# Yombonet.net
KiCad netlist of a schematic drawn in EAGLE
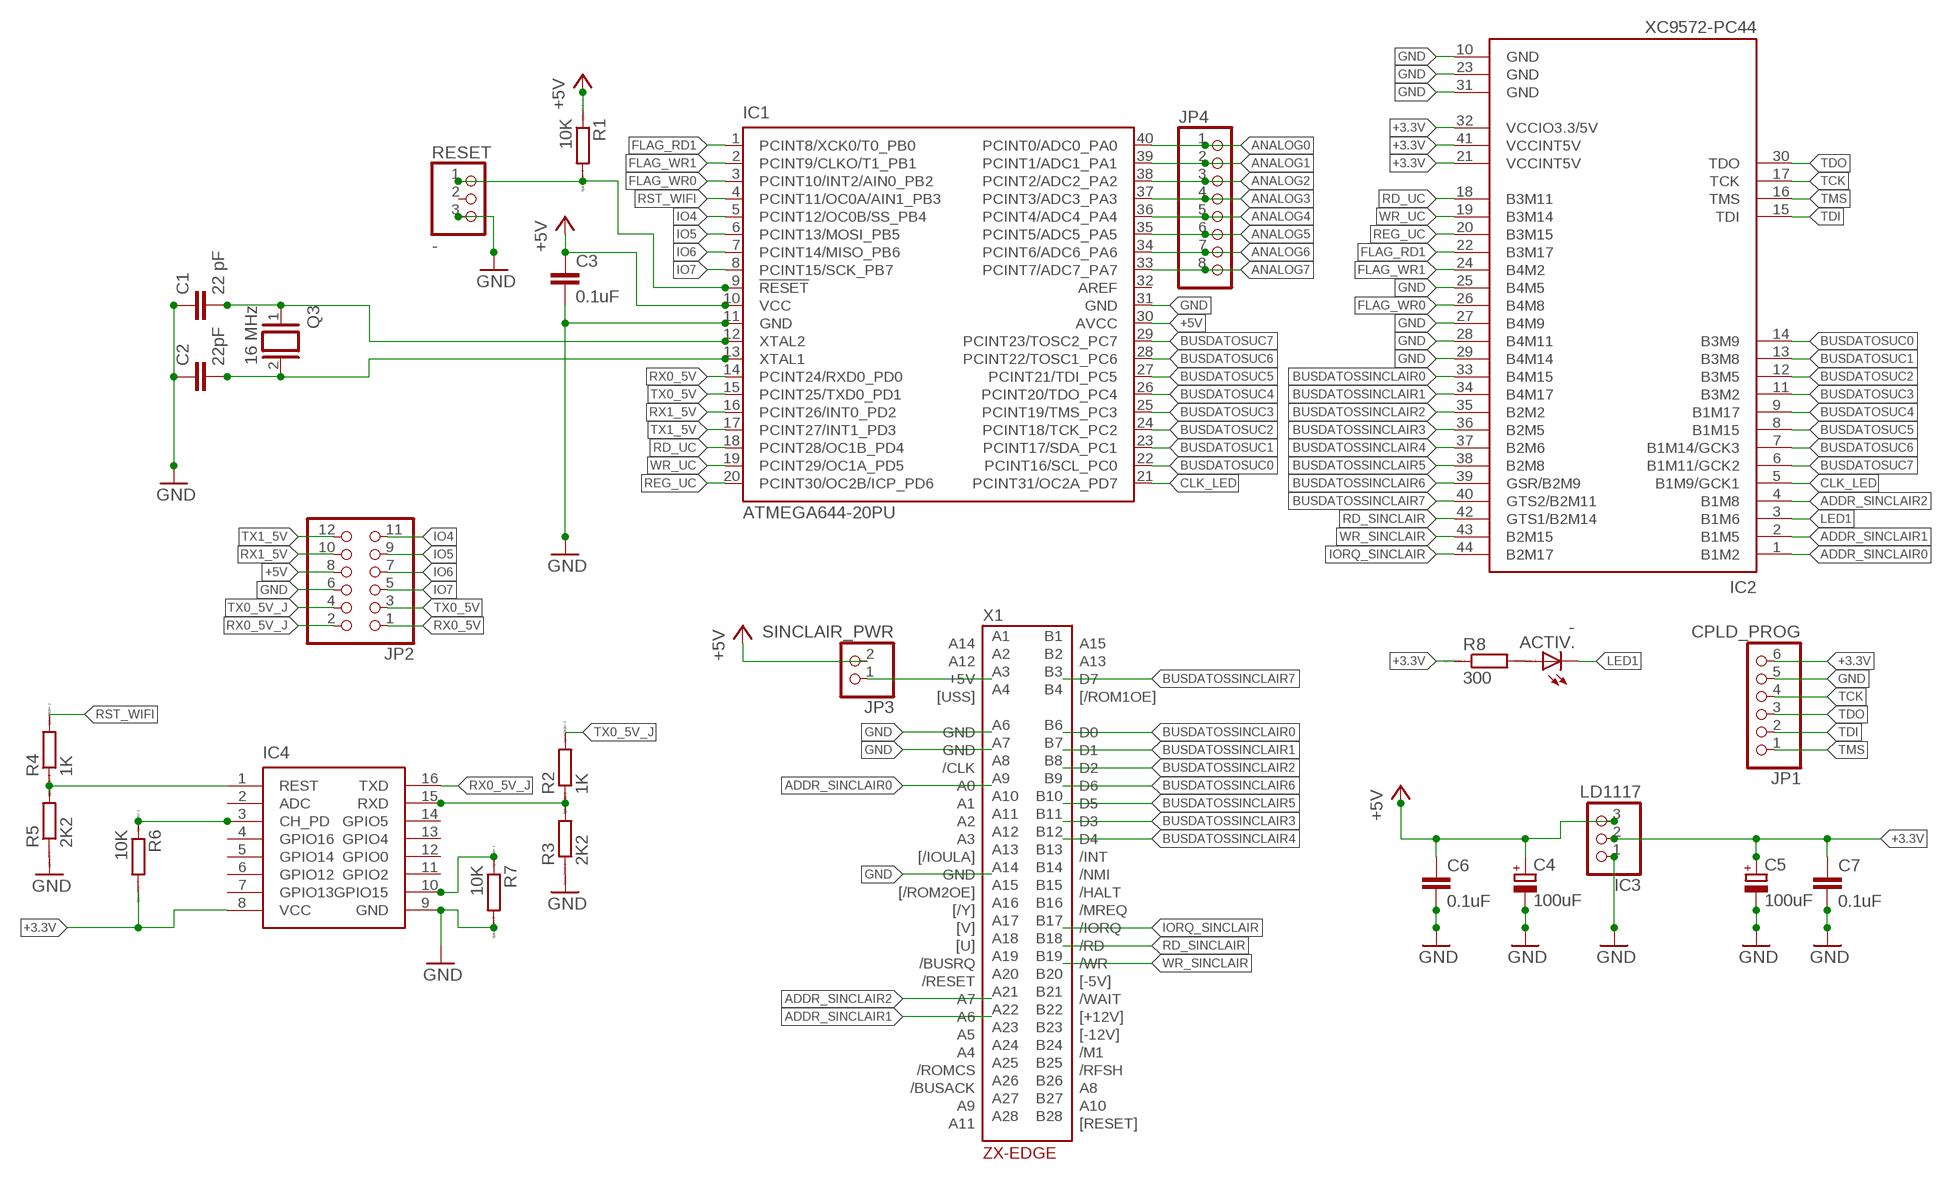
[diagram p0: schematic, sheet 1]

(export (version "E")
  (design (tool "Eeschema 10.0.6"))
  (components
    (comp (ref "ACTIV.")
      (value "-")
      (footprint "eagle-import:LED3MM")
      (libsource (lib "eagle-import") (part "LED3MM"))
    )
    (comp (ref "C1")
      (value "22 pF")
      (footprint "eagle-import:C025-024X044")
      (libsource (lib "eagle-import") (part "C-EU025-024X044"))
    )
    (comp (ref "C2")
      (value "22pF")
      (footprint "eagle-import:C025-024X044")
      (libsource (lib "eagle-import") (part "C-EU025-024X044"))
    )
    (comp (ref "C3")
      (value "0.1uF")
      (footprint "eagle-import:C025-025X050")
      (libsource (lib "eagle-import") (part "C-EU025-025X050"))
    )
    (comp (ref "C4")
      (value "100uF")
      (footprint "eagle-import:E2,5-7")
      (libsource (lib "eagle-import") (part "CPOL-EUE2.5-7"))
    )
    (comp (ref "C5")
      (value "100uF")
      (footprint "eagle-import:E2,5-7")
      (libsource (lib "eagle-import") (part "CPOL-EUE2.5-7"))
    )
    (comp (ref "C6")
      (value "0.1uF")
      (footprint "eagle-import:C025-025X050")
      (libsource (lib "eagle-import") (part "C-EU025-025X050"))
    )
    (comp (ref "C7")
      (value "0.1uF")
      (footprint "eagle-import:C025-025X050")
      (libsource (lib "eagle-import") (part "C-EU025-025X050"))
    )
    (comp (ref "IC1")
      (value "ATMEGA644-20PU")
      (footprint "eagle-import:DIL40")
      (libsource (lib "eagle-import") (part "ATMEGA644-PU20"))
    )
    (comp (ref "IC2")
      (value "XC9572-PC44")
      (footprint "eagle-import:PLCC-S44")
      (libsource (lib "eagle-import") (part "XC9572-PC44"))
    )
    (comp (ref "IC3")
      (value "LD1117")
      (footprint "eagle-import:1X03")
      (libsource (lib "eagle-import") (part "PINHD-1X3"))
    )
    (comp (ref "IC4")
      (value "ESP-07ESP-07")
      (footprint "eagle-import:ESP-07")
      (libsource (lib "eagle-import") (part "ESP-07ESP-07"))
    )
    (comp (ref "JP1")
      (value "CPLD_PROG")
      (footprint "eagle-import:1X06")
      (libsource (lib "eagle-import") (part "PINHD-1X6"))
    )
    (comp (ref "JP2")
      (value "PINHD-2X6")
      (footprint "eagle-import:2X06")
      (libsource (lib "eagle-import") (part "PINHD-2X6"))
    )
    (comp (ref "JP3")
      (value "SINCLAIR_PWR")
      (footprint "eagle-import:1X02")
      (libsource (lib "eagle-import") (part "PINHD-1X2"))
    )
    (comp (ref "JP4")
      (value "PINHD-1X8")
      (footprint "eagle-import:1X08")
      (libsource (lib "eagle-import") (part "PINHD-1X8"))
    )
    (comp (ref "Q3")
      (value "16 MHz")
      (footprint "eagle-import:QS")
      (libsource (lib "eagle-import") (part "XTAL/S"))
    )
    (comp (ref "R1")
      (value "10K")
      (footprint "eagle-import:0207_10")
      (libsource (lib "eagle-import") (part "R-EU_0207_10"))
    )
    (comp (ref "R2")
      (value "1K")
      (footprint "eagle-import:0207_10")
      (libsource (lib "eagle-import") (part "R-EU_0207_10"))
    )
    (comp (ref "R3")
      (value "2K2")
      (footprint "eagle-import:0207_10")
      (libsource (lib "eagle-import") (part "R-EU_0207_10"))
    )
    (comp (ref "R4")
      (value "1K")
      (footprint "eagle-import:0207_10")
      (libsource (lib "eagle-import") (part "R-EU_0207_10"))
    )
    (comp (ref "R5")
      (value "2K2")
      (footprint "eagle-import:0207_10")
      (libsource (lib "eagle-import") (part "R-EU_0207_10"))
    )
    (comp (ref "R6")
      (value "10K")
      (footprint "eagle-import:0207_10")
      (libsource (lib "eagle-import") (part "R-EU_0207_10"))
    )
    (comp (ref "R7")
      (value "10K")
      (footprint "eagle-import:0207_10")
      (libsource (lib "eagle-import") (part "R-EU_0207_10"))
    )
    (comp (ref "R8")
      (value "300")
      (footprint "eagle-import:0207_10")
      (libsource (lib "eagle-import") (part "R-EU_0207_10"))
    )
    (comp (ref "RESET")
      (value "-")
      (footprint "eagle-import:1X03")
      (libsource (lib "eagle-import") (part "PINHD-1X3"))
    )
    (comp (ref "X1")
      (value "ZX-EDGE")
      (footprint "eagle-import:ZX-IFACE")
      (libsource (lib "eagle-import") (part "ZX-EDGE"))
    )
  )
  (nets
    (net (code "1") (name "+3.3V") (class "Default")
      (node (ref "C5") (pin "+") (pinfunction "+_+") (pintype "passive"))
      (node (ref "C7") (pin "1") (pinfunction "1_1") (pintype "passive"))
      (node (ref "IC2") (pin "21") (pinfunction "VCCINT5V_21") (pintype "bidirectional"))
      (node (ref "IC2") (pin "32") (pinfunction "VCCIO3.3/5V_32") (pintype "bidirectional"))
      (node (ref "IC2") (pin "41") (pinfunction "VCCINT5V_41") (pintype "bidirectional"))
      (node (ref "IC3") (pin "2") (pinfunction "2_2") (pintype "passive"))
      (node (ref "IC4") (pin "8") (pinfunction "VCC_8") (pintype "power_in"))
      (node (ref "JP1") (pin "6") (pinfunction "6_6") (pintype "passive"))
      (node (ref "R6") (pin "2") (pinfunction "2_2") (pintype "passive"))
      (node (ref "R8") (pin "1") (pinfunction "1_1") (pintype "passive"))
    )
    (net (code "2") (name "+5V") (class "Default")
      (node (ref "C3") (pin "1") (pinfunction "1_1") (pintype "passive"))
      (node (ref "C4") (pin "+") (pinfunction "+_+") (pintype "passive"))
      (node (ref "C6") (pin "1") (pinfunction "1_1") (pintype "passive"))
      (node (ref "IC1") (pin "10") (pinfunction "VCC_10") (pintype "power_in"))
      (node (ref "IC1") (pin "30") (pinfunction "AVCC_30") (pintype "power_in"))
      (node (ref "IC3") (pin "3") (pinfunction "3_3") (pintype "passive"))
      (node (ref "JP2") (pin "8") (pinfunction "8_8") (pintype "passive"))
      (node (ref "JP3") (pin "2") (pinfunction "2_2") (pintype "passive"))
      (node (ref "R1") (pin "1") (pinfunction "1_1") (pintype "passive"))
    )
    (net (code "3") (name "ADDR_SINCLAIR0") (class "Default")
      (node (ref "IC2") (pin "1") (pinfunction "B1M2_1") (pintype "bidirectional"))
      (node (ref "X1") (pin "A9") (pinfunction "A0_A9") (pintype "bidirectional"))
    )
    (net (code "4") (name "ADDR_SINCLAIR1") (class "Default")
      (node (ref "IC2") (pin "2") (pinfunction "B1M5_2") (pintype "bidirectional"))
      (node (ref "X1") (pin "A22") (pinfunction "A6_A22") (pintype "bidirectional"))
    )
    (net (code "5") (name "ADDR_SINCLAIR2") (class "Default")
      (node (ref "IC2") (pin "4") (pinfunction "B1M8_4") (pintype "bidirectional"))
      (node (ref "X1") (pin "A21") (pinfunction "A7_A21") (pintype "bidirectional"))
    )
    (net (code "6") (name "ANALOG0") (class "Default")
      (node (ref "IC1") (pin "40") (pinfunction "PCINT0/ADC0_PA0_40") (pintype "bidirectional"))
      (node (ref "JP4") (pin "1") (pinfunction "1_1") (pintype "passive"))
    )
    (net (code "7") (name "ANALOG1") (class "Default")
      (node (ref "IC1") (pin "39") (pinfunction "PCINT1/ADC1_PA1_39") (pintype "bidirectional"))
      (node (ref "JP4") (pin "2") (pinfunction "2_2") (pintype "passive"))
    )
    (net (code "8") (name "ANALOG2") (class "Default")
      (node (ref "IC1") (pin "38") (pinfunction "PCINT2/ADC2_PA2_38") (pintype "bidirectional"))
      (node (ref "JP4") (pin "3") (pinfunction "3_3") (pintype "passive"))
    )
    (net (code "9") (name "ANALOG3") (class "Default")
      (node (ref "IC1") (pin "37") (pinfunction "PCINT3/ADC3_PA3_37") (pintype "bidirectional"))
      (node (ref "JP4") (pin "4") (pinfunction "4_4") (pintype "passive"))
    )
    (net (code "10") (name "ANALOG4") (class "Default")
      (node (ref "IC1") (pin "36") (pinfunction "PCINT4/ADC4_PA4_36") (pintype "bidirectional"))
      (node (ref "JP4") (pin "5") (pinfunction "5_5") (pintype "passive"))
    )
    (net (code "11") (name "ANALOG5") (class "Default")
      (node (ref "IC1") (pin "35") (pinfunction "PCINT5/ADC5_PA5_35") (pintype "bidirectional"))
      (node (ref "JP4") (pin "6") (pinfunction "6_6") (pintype "passive"))
    )
    (net (code "12") (name "ANALOG6") (class "Default")
      (node (ref "IC1") (pin "34") (pinfunction "PCINT6/ADC6_PA6_34") (pintype "bidirectional"))
      (node (ref "JP4") (pin "7") (pinfunction "7_7") (pintype "passive"))
    )
    (net (code "13") (name "ANALOG7") (class "Default")
      (node (ref "IC1") (pin "33") (pinfunction "PCINT7/ADC7_PA7_33") (pintype "bidirectional"))
      (node (ref "JP4") (pin "8") (pinfunction "8_8") (pintype "passive"))
    )
    (net (code "14") (name "BUSDATOSSINCLAIR0") (class "Default")
      (node (ref "IC2") (pin "33") (pinfunction "B4M15_33") (pintype "bidirectional"))
      (node (ref "X1") (pin "B6") (pinfunction "D0_B6") (pintype "bidirectional"))
    )
    (net (code "15") (name "BUSDATOSSINCLAIR1") (class "Default")
      (node (ref "IC2") (pin "34") (pinfunction "B4M17_34") (pintype "bidirectional"))
      (node (ref "X1") (pin "B7") (pinfunction "D1_B7") (pintype "bidirectional"))
    )
    (net (code "16") (name "BUSDATOSSINCLAIR2") (class "Default")
      (node (ref "IC2") (pin "35") (pinfunction "B2M2_35") (pintype "bidirectional"))
      (node (ref "X1") (pin "B8") (pinfunction "D2_B8") (pintype "bidirectional"))
    )
    (net (code "17") (name "BUSDATOSSINCLAIR3") (class "Default")
      (node (ref "IC2") (pin "36") (pinfunction "B2M5_36") (pintype "bidirectional"))
      (node (ref "X1") (pin "B11") (pinfunction "D3_B11") (pintype "bidirectional"))
    )
    (net (code "18") (name "BUSDATOSSINCLAIR4") (class "Default")
      (node (ref "IC2") (pin "37") (pinfunction "B2M6_37") (pintype "bidirectional"))
      (node (ref "X1") (pin "B12") (pinfunction "D4_B12") (pintype "bidirectional"))
    )
    (net (code "19") (name "BUSDATOSSINCLAIR5") (class "Default")
      (node (ref "IC2") (pin "38") (pinfunction "B2M8_38") (pintype "bidirectional"))
      (node (ref "X1") (pin "B10") (pinfunction "D5_B10") (pintype "bidirectional"))
    )
    (net (code "20") (name "BUSDATOSSINCLAIR6") (class "Default")
      (node (ref "IC2") (pin "39") (pinfunction "GSR/B2M9_39") (pintype "bidirectional"))
      (node (ref "X1") (pin "B9") (pinfunction "D6_B9") (pintype "bidirectional"))
    )
    (net (code "21") (name "BUSDATOSSINCLAIR7") (class "Default")
      (node (ref "IC2") (pin "40") (pinfunction "GTS2/B2M11_40") (pintype "bidirectional"))
      (node (ref "X1") (pin "B3") (pinfunction "D7_B3") (pintype "bidirectional"))
    )
    (net (code "22") (name "BUSDATOSUC0") (class "Default")
      (node (ref "IC1") (pin "22") (pinfunction "PCINT16/SCL_PC0_22") (pintype "bidirectional"))
      (node (ref "IC2") (pin "14") (pinfunction "B3M9_14") (pintype "bidirectional"))
    )
    (net (code "23") (name "BUSDATOSUC1") (class "Default")
      (node (ref "IC1") (pin "23") (pinfunction "PCINT17/SDA_PC1_23") (pintype "bidirectional"))
      (node (ref "IC2") (pin "13") (pinfunction "B3M8_13") (pintype "bidirectional"))
    )
    (net (code "24") (name "BUSDATOSUC2") (class "Default")
      (node (ref "IC1") (pin "24") (pinfunction "PCINT18/TCK_PC2_24") (pintype "bidirectional"))
      (node (ref "IC2") (pin "12") (pinfunction "B3M5_12") (pintype "bidirectional"))
    )
    (net (code "25") (name "BUSDATOSUC3") (class "Default")
      (node (ref "IC1") (pin "25") (pinfunction "PCINT19/TMS_PC3_25") (pintype "bidirectional"))
      (node (ref "IC2") (pin "11") (pinfunction "B3M2_11") (pintype "bidirectional"))
    )
    (net (code "26") (name "BUSDATOSUC4") (class "Default")
      (node (ref "IC1") (pin "26") (pinfunction "PCINT20/TDO_PC4_26") (pintype "bidirectional"))
      (node (ref "IC2") (pin "9") (pinfunction "B1M17_9") (pintype "bidirectional"))
    )
    (net (code "27") (name "BUSDATOSUC5") (class "Default")
      (node (ref "IC1") (pin "27") (pinfunction "PCINT21/TDI_PC5_27") (pintype "bidirectional"))
      (node (ref "IC2") (pin "8") (pinfunction "B1M15_8") (pintype "bidirectional"))
    )
    (net (code "28") (name "BUSDATOSUC6") (class "Default")
      (node (ref "IC1") (pin "28") (pinfunction "PCINT22/TOSC1_PC6_28") (pintype "bidirectional"))
      (node (ref "IC2") (pin "7") (pinfunction "B1M14/GCK3_7") (pintype "bidirectional"))
    )
    (net (code "29") (name "BUSDATOSUC7") (class "Default")
      (node (ref "IC1") (pin "29") (pinfunction "PCINT23/TOSC2_PC7_29") (pintype "bidirectional"))
      (node (ref "IC2") (pin "6") (pinfunction "B1M11/GCK2_6") (pintype "bidirectional"))
    )
    (net (code "30") (name "CLK_LED") (class "Default")
      (node (ref "IC1") (pin "21") (pinfunction "PCINT31/OC2A_PD7_21") (pintype "bidirectional"))
      (node (ref "IC2") (pin "5") (pinfunction "B1M9/GCK1_5") (pintype "bidirectional"))
    )
    (net (code "31") (name "FLAG_RD1") (class "Default")
      (node (ref "IC1") (pin "1") (pinfunction "PCINT8/XCK0/T0_PB0_1") (pintype "bidirectional"))
      (node (ref "IC2") (pin "22") (pinfunction "B3M17_22") (pintype "bidirectional"))
    )
    (net (code "32") (name "FLAG_WR0") (class "Default")
      (node (ref "IC1") (pin "3") (pinfunction "PCINT10/INT2/AIN0_PB2_3") (pintype "bidirectional"))
      (node (ref "IC2") (pin "26") (pinfunction "B4M8_26") (pintype "bidirectional"))
    )
    (net (code "33") (name "FLAG_WR1") (class "Default")
      (node (ref "IC1") (pin "2") (pinfunction "PCINT9/CLKO/T1_PB1_2") (pintype "bidirectional"))
      (node (ref "IC2") (pin "24") (pinfunction "B4M2_24") (pintype "bidirectional"))
    )
    (net (code "34") (name "GND") (class "Default")
      (node (ref "C1") (pin "1") (pinfunction "1_1") (pintype "passive"))
      (node (ref "C2") (pin "1") (pinfunction "1_1") (pintype "passive"))
      (node (ref "C3") (pin "2") (pinfunction "2_2") (pintype "passive"))
      (node (ref "C4") (pin "-") (pinfunction "-_-") (pintype "passive"))
      (node (ref "C5") (pin "-") (pinfunction "-_-") (pintype "passive"))
      (node (ref "C6") (pin "2") (pinfunction "2_2") (pintype "passive"))
      (node (ref "C7") (pin "2") (pinfunction "2_2") (pintype "passive"))
      (node (ref "IC1") (pin "11") (pinfunction "GND_11") (pintype "power_in"))
      (node (ref "IC1") (pin "31") (pinfunction "GND_31") (pintype "power_in"))
      (node (ref "IC2") (pin "10") (pinfunction "GND_10") (pintype "bidirectional"))
      (node (ref "IC2") (pin "23") (pinfunction "GND_23") (pintype "bidirectional"))
      (node (ref "IC2") (pin "25") (pinfunction "B4M5_25") (pintype "bidirectional"))
      (node (ref "IC2") (pin "27") (pinfunction "B4M9_27") (pintype "bidirectional"))
      (node (ref "IC2") (pin "28") (pinfunction "B4M11_28") (pintype "bidirectional"))
      (node (ref "IC2") (pin "29") (pinfunction "B4M14_29") (pintype "bidirectional"))
      (node (ref "IC2") (pin "31") (pinfunction "GND_31") (pintype "bidirectional"))
      (node (ref "IC3") (pin "1") (pinfunction "1_1") (pintype "passive"))
      (node (ref "IC4") (pin "9") (pinfunction "GND_9") (pintype "power_in"))
      (node (ref "JP1") (pin "5") (pinfunction "5_5") (pintype "passive"))
      (node (ref "JP2") (pin "6") (pinfunction "6_6") (pintype "passive"))
      (node (ref "R3") (pin "1") (pinfunction "1_1") (pintype "passive"))
      (node (ref "R5") (pin "1") (pinfunction "1_1") (pintype "passive"))
      (node (ref "R7") (pin "2") (pinfunction "2_2") (pintype "passive"))
      (node (ref "RESET") (pin "3") (pinfunction "3_3") (pintype "passive"))
      (node (ref "X1") (pin "A14") (pinfunction "GND_A14") (pintype "bidirectional"))
      (node (ref "X1") (pin "A6") (pinfunction "GND_A6") (pintype "bidirectional"))
      (node (ref "X1") (pin "A7") (pinfunction "GND_A7") (pintype "bidirectional"))
    )
    (net (code "35") (name "IO4") (class "Default")
      (node (ref "IC1") (pin "5") (pinfunction "PCINT12/OC0B/SS_PB4_5") (pintype "bidirectional"))
      (node (ref "JP2") (pin "11") (pinfunction "11_11") (pintype "passive"))
    )
    (net (code "36") (name "IO5") (class "Default")
      (node (ref "IC1") (pin "6") (pinfunction "PCINT13/MOSI_PB5_6") (pintype "bidirectional"))
      (node (ref "JP2") (pin "9") (pinfunction "9_9") (pintype "passive"))
    )
    (net (code "37") (name "IO6") (class "Default")
      (node (ref "IC1") (pin "7") (pinfunction "PCINT14/MISO_PB6_7") (pintype "bidirectional"))
      (node (ref "JP2") (pin "7") (pinfunction "7_7") (pintype "passive"))
    )
    (net (code "38") (name "IO7") (class "Default")
      (node (ref "IC1") (pin "8") (pinfunction "PCINT15/SCK_PB7_8") (pintype "bidirectional"))
      (node (ref "JP2") (pin "5") (pinfunction "5_5") (pintype "passive"))
    )
    (net (code "39") (name "IORQ_SINCLAIR") (class "Default")
      (node (ref "IC2") (pin "44") (pinfunction "B2M17_44") (pintype "bidirectional"))
      (node (ref "X1") (pin "B17") (pinfunction "/IORQ_B17") (pintype "bidirectional"))
    )
    (net (code "40") (name "LED1") (class "Default")
      (node (ref "ACTIV.") (pin "K") (pinfunction "C_K") (pintype "passive"))
      (node (ref "IC2") (pin "3") (pinfunction "B1M6_3") (pintype "bidirectional"))
    )
    (net (code "41") (name "Net-(ACTIV.-PadA)") (class "Default")
      (node (ref "ACTIV.") (pin "A") (pinfunction "A_A") (pintype "passive"))
      (node (ref "R8") (pin "2") (pinfunction "2_2") (pintype "passive"))
    )
    (net (code "42") (name "Net-(IC1-XTAL1)") (class "Default")
      (node (ref "C2") (pin "2") (pinfunction "2_2") (pintype "passive"))
      (node (ref "IC1") (pin "13") (pinfunction "XTAL1_13") (pintype "input"))
      (node (ref "Q3") (pin "2") (pinfunction "2_2") (pintype "passive"))
    )
    (net (code "43") (name "Net-(IC1-XTAL2)") (class "Default")
      (node (ref "C1") (pin "2") (pinfunction "2_2") (pintype "passive"))
      (node (ref "IC1") (pin "12") (pinfunction "XTAL2_12") (pintype "output"))
      (node (ref "Q3") (pin "1") (pinfunction "1_1") (pintype "passive"))
    )
    (net (code "44") (name "Net-(IC1-~{RESET})") (class "Default")
      (node (ref "IC1") (pin "9") (pinfunction "~{RESET}_9") (pintype "input"))
      (node (ref "R1") (pin "2") (pinfunction "2_2") (pintype "passive"))
      (node (ref "RESET") (pin "1") (pinfunction "1_1") (pintype "passive"))
    )
    (net (code "45") (name "Net-(IC4-CH_PD)") (class "Default")
      (node (ref "IC4") (pin "3") (pinfunction "CH_PD_3") (pintype "bidirectional"))
      (node (ref "R6") (pin "1") (pinfunction "1_1") (pintype "passive"))
    )
    (net (code "46") (name "Net-(IC4-GPIO15)") (class "Default")
      (node (ref "IC4") (pin "10") (pinfunction "GPIO15_10") (pintype "bidirectional"))
      (node (ref "R7") (pin "1") (pinfunction "1_1") (pintype "passive"))
    )
    (net (code "47") (name "Net-(IC4-REST)") (class "Default")
      (node (ref "IC4") (pin "1") (pinfunction "REST_1") (pintype "input"))
      (node (ref "R4") (pin "1") (pinfunction "1_1") (pintype "passive"))
      (node (ref "R5") (pin "2") (pinfunction "2_2") (pintype "passive"))
    )
    (net (code "48") (name "Net-(IC4-RXD)") (class "Default")
      (node (ref "IC4") (pin "15") (pinfunction "RXD_15") (pintype "input"))
      (node (ref "R2") (pin "1") (pinfunction "1_1") (pintype "passive"))
      (node (ref "R3") (pin "2") (pinfunction "2_2") (pintype "passive"))
    )
    (net (code "49") (name "Net-(X1-+5V)") (class "Default")
      (node (ref "JP3") (pin "1") (pinfunction "1_1") (pintype "passive"))
      (node (ref "X1") (pin "A3") (pinfunction "+5V_A3") (pintype "bidirectional"))
    )
    (net (code "50") (name "RD_SINCLAIR") (class "Default")
      (node (ref "IC2") (pin "42") (pinfunction "GTS1/B2M14_42") (pintype "bidirectional"))
      (node (ref "X1") (pin "B18") (pinfunction "/RD_B18") (pintype "bidirectional"))
    )
    (net (code "51") (name "RD_UC") (class "Default")
      (node (ref "IC1") (pin "18") (pinfunction "PCINT28/OC1B_PD4_18") (pintype "bidirectional"))
      (node (ref "IC2") (pin "18") (pinfunction "B3M11_18") (pintype "bidirectional"))
    )
    (net (code "52") (name "REG_UC") (class "Default")
      (node (ref "IC1") (pin "20") (pinfunction "PCINT30/OC2B/ICP_PD6_20") (pintype "bidirectional"))
      (node (ref "IC2") (pin "20") (pinfunction "B3M15_20") (pintype "bidirectional"))
    )
    (net (code "53") (name "RST_WIFI") (class "Default")
      (node (ref "IC1") (pin "4") (pinfunction "PCINT11/OC0A/AIN1_PB3_4") (pintype "bidirectional"))
      (node (ref "R4") (pin "2") (pinfunction "2_2") (pintype "passive"))
    )
    (net (code "54") (name "RX0_5V") (class "Default")
      (node (ref "IC1") (pin "14") (pinfunction "PCINT24/RXD0_PD0_14") (pintype "bidirectional"))
      (node (ref "JP2") (pin "1") (pinfunction "1_1") (pintype "passive"))
    )
    (net (code "55") (name "RX0_5V_J") (class "Default")
      (node (ref "IC4") (pin "16") (pinfunction "TXD_16") (pintype "output"))
      (node (ref "JP2") (pin "2") (pinfunction "2_2") (pintype "passive"))
    )
    (net (code "56") (name "RX1_5V") (class "Default")
      (node (ref "IC1") (pin "16") (pinfunction "PCINT26/INT0_PD2_16") (pintype "bidirectional"))
      (node (ref "JP2") (pin "10") (pinfunction "10_10") (pintype "passive"))
    )
    (net (code "57") (name "TCK") (class "Default")
      (node (ref "IC2") (pin "17") (pinfunction "TCK_17") (pintype "bidirectional"))
      (node (ref "JP1") (pin "4") (pinfunction "4_4") (pintype "passive"))
    )
    (net (code "58") (name "TDI") (class "Default")
      (node (ref "IC2") (pin "15") (pinfunction "TDI_15") (pintype "bidirectional"))
      (node (ref "JP1") (pin "2") (pinfunction "2_2") (pintype "passive"))
    )
    (net (code "59") (name "TDO") (class "Default")
      (node (ref "IC2") (pin "30") (pinfunction "TDO_30") (pintype "bidirectional"))
      (node (ref "JP1") (pin "3") (pinfunction "3_3") (pintype "passive"))
    )
    (net (code "60") (name "TMS") (class "Default")
      (node (ref "IC2") (pin "16") (pinfunction "TMS_16") (pintype "bidirectional"))
      (node (ref "JP1") (pin "1") (pinfunction "1_1") (pintype "passive"))
    )
    (net (code "61") (name "TX0_5V") (class "Default")
      (node (ref "IC1") (pin "15") (pinfunction "PCINT25/TXD0_PD1_15") (pintype "bidirectional"))
      (node (ref "JP2") (pin "3") (pinfunction "3_3") (pintype "passive"))
    )
    (net (code "62") (name "TX0_5V_J") (class "Default")
      (node (ref "JP2") (pin "4") (pinfunction "4_4") (pintype "passive"))
      (node (ref "R2") (pin "2") (pinfunction "2_2") (pintype "passive"))
    )
    (net (code "63") (name "TX1_5V") (class "Default")
      (node (ref "IC1") (pin "17") (pinfunction "PCINT27/INT1_PD3_17") (pintype "bidirectional"))
      (node (ref "JP2") (pin "12") (pinfunction "12_12") (pintype "passive"))
    )
    (net (code "64") (name "WR_SINCLAIR") (class "Default")
      (node (ref "IC2") (pin "43") (pinfunction "B2M15_43") (pintype "bidirectional"))
      (node (ref "X1") (pin "B19") (pinfunction "/WR_B19") (pintype "bidirectional"))
    )
    (net (code "65") (name "WR_UC") (class "Default")
      (node (ref "IC1") (pin "19") (pinfunction "PCINT29/OC1A_PD5_19") (pintype "bidirectional"))
      (node (ref "IC2") (pin "19") (pinfunction "B3M14_19") (pintype "bidirectional"))
    )
    (net (code "66") (name "unconnected-(IC1-AREF-Pad32)") (class "Default")
      (node (ref "IC1") (pin "32") (pinfunction "AREF_32") (pintype "passive"))
    )
    (net (code "67") (name "unconnected-(IC4-ADC-Pad2)") (class "Default")
      (node (ref "IC4") (pin "2") (pinfunction "ADC_2") (pintype "bidirectional"))
    )
    (net (code "68") (name "unconnected-(IC4-GPIO0-Pad12)") (class "Default")
      (node (ref "IC4") (pin "12") (pinfunction "GPIO0_12") (pintype "bidirectional"))
    )
    (net (code "69") (name "unconnected-(IC4-GPIO2-Pad11)") (class "Default")
      (node (ref "IC4") (pin "11") (pinfunction "GPIO2_11") (pintype "bidirectional"))
    )
    (net (code "70") (name "unconnected-(IC4-GPIO4-Pad13)") (class "Default")
      (node (ref "IC4") (pin "13") (pinfunction "GPIO4_13") (pintype "bidirectional"))
    )
    (net (code "71") (name "unconnected-(IC4-GPIO5-Pad14)") (class "Default")
      (node (ref "IC4") (pin "14") (pinfunction "GPIO5_14") (pintype "bidirectional"))
    )
    (net (code "72") (name "unconnected-(IC4-GPIO12-Pad6)") (class "Default")
      (node (ref "IC4") (pin "6") (pinfunction "GPIO12_6") (pintype "bidirectional"))
    )
    (net (code "73") (name "unconnected-(IC4-GPIO13-Pad7)") (class "Default")
      (node (ref "IC4") (pin "7") (pinfunction "GPIO13_7") (pintype "bidirectional"))
    )
    (net (code "74") (name "unconnected-(IC4-GPIO14-Pad5)") (class "Default")
      (node (ref "IC4") (pin "5") (pinfunction "GPIO14_5") (pintype "bidirectional"))
    )
    (net (code "75") (name "unconnected-(IC4-GPIO16-Pad4)") (class "Default")
      (node (ref "IC4") (pin "4") (pinfunction "GPIO16_4") (pintype "bidirectional"))
    )
    (net (code "76") (name "unconnected-(RESET-Pad2)") (class "Default")
      (node (ref "RESET") (pin "2") (pinfunction "2_2") (pintype "passive"))
    )
    (net (code "77") (name "unconnected-(X1-A1-PadA10)") (class "Default")
      (node (ref "X1") (pin "A10") (pinfunction "A1_A10") (pintype "bidirectional"))
    )
    (net (code "78") (name "unconnected-(X1-A2-PadA11)") (class "Default")
      (node (ref "X1") (pin "A11") (pinfunction "A2_A11") (pintype "bidirectional"))
    )
    (net (code "79") (name "unconnected-(X1-A3-PadA12)") (class "Default")
      (node (ref "X1") (pin "A12") (pinfunction "A3_A12") (pintype "bidirectional"))
    )
    (net (code "80") (name "unconnected-(X1-A4-PadA24)") (class "Default")
      (node (ref "X1") (pin "A24") (pinfunction "A4_A24") (pintype "bidirectional"))
    )
    (net (code "81") (name "unconnected-(X1-A5-PadA23)") (class "Default")
      (node (ref "X1") (pin "A23") (pinfunction "A5_A23") (pintype "bidirectional"))
    )
    (net (code "82") (name "unconnected-(X1-A8-PadB26)") (class "Default")
      (node (ref "X1") (pin "B26") (pinfunction "A8_B26") (pintype "bidirectional"))
    )
    (net (code "83") (name "unconnected-(X1-A9-PadA27)") (class "Default")
      (node (ref "X1") (pin "A27") (pinfunction "A9_A27") (pintype "bidirectional"))
    )
    (net (code "84") (name "unconnected-(X1-A10-PadB27)") (class "Default")
      (node (ref "X1") (pin "B27") (pinfunction "A10_B27") (pintype "bidirectional"))
    )
    (net (code "85") (name "unconnected-(X1-A11-PadA28)") (class "Default")
      (node (ref "X1") (pin "A28") (pinfunction "A11_A28") (pintype "bidirectional"))
    )
    (net (code "86") (name "unconnected-(X1-A12-PadA2)") (class "Default")
      (node (ref "X1") (pin "A2") (pinfunction "A12_A2") (pintype "bidirectional"))
    )
    (net (code "87") (name "unconnected-(X1-A13-PadB2)") (class "Default")
      (node (ref "X1") (pin "B2") (pinfunction "A13_B2") (pintype "bidirectional"))
    )
    (net (code "88") (name "unconnected-(X1-A14-PadA1)") (class "Default")
      (node (ref "X1") (pin "A1") (pinfunction "A14_A1") (pintype "bidirectional"))
    )
    (net (code "89") (name "unconnected-(X1-A15-PadB1)") (class "Default")
      (node (ref "X1") (pin "B1") (pinfunction "A15_B1") (pintype "bidirectional"))
    )
    (net (code "90") (name "unconnected-(X1-[+12V]-PadB22)") (class "Default")
      (node (ref "X1") (pin "B22") (pinfunction "[+12V]_B22") (pintype "bidirectional"))
    )
    (net (code "91") (name "unconnected-(X1-[-5V]-PadB20)") (class "Default")
      (node (ref "X1") (pin "B20") (pinfunction "[-5V]_B20") (pintype "bidirectional"))
    )
    (net (code "92") (name "unconnected-(X1-[-12V]-PadB23)") (class "Default")
      (node (ref "X1") (pin "B23") (pinfunction "[-12V]_B23") (pintype "bidirectional"))
    )
    (net (code "93") (name "unconnected-(X1-[RESET]-PadB28)") (class "Default")
      (node (ref "X1") (pin "B28") (pinfunction "[RESET]_B28") (pintype "bidirectional"))
    )
    (net (code "94") (name "unconnected-(X1-[USS]-PadA4)") (class "Default")
      (node (ref "X1") (pin "A4") (pinfunction "[USS]_A4") (pintype "bidirectional"))
    )
    (net (code "95") (name "unconnected-(X1-[U]-PadA18)") (class "Default")
      (node (ref "X1") (pin "A18") (pinfunction "[U]_A18") (pintype "bidirectional"))
    )
    (net (code "96") (name "unconnected-(X1-[V]-PadA17)") (class "Default")
      (node (ref "X1") (pin "A17") (pinfunction "[V]_A17") (pintype "bidirectional"))
    )
    (net (code "97") (name "unconnected-(X1-[{slash}IOULA]-PadA13)") (class "Default")
      (node (ref "X1") (pin "A13") (pinfunction "[/IOULA]_A13") (pintype "bidirectional"))
    )
    (net (code "98") (name "unconnected-(X1-[{slash}ROM1OE]-PadB4)") (class "Default")
      (node (ref "X1") (pin "B4") (pinfunction "[/ROM1OE]_B4") (pintype "bidirectional"))
    )
    (net (code "99") (name "unconnected-(X1-[{slash}ROM2OE]-PadA15)") (class "Default")
      (node (ref "X1") (pin "A15") (pinfunction "[/ROM2OE]_A15") (pintype "bidirectional"))
    )
    (net (code "100") (name "unconnected-(X1-[{slash}Y]-PadA16)") (class "Default")
      (node (ref "X1") (pin "A16") (pinfunction "[/Y]_A16") (pintype "bidirectional"))
    )
    (net (code "101") (name "unconnected-(X1-{slash}BUSACK-PadA26)") (class "Default")
      (node (ref "X1") (pin "A26") (pinfunction "/BUSACK_A26") (pintype "bidirectional"))
    )
    (net (code "102") (name "unconnected-(X1-{slash}BUSRQ-PadA19)") (class "Default")
      (node (ref "X1") (pin "A19") (pinfunction "/BUSRQ_A19") (pintype "bidirectional"))
    )
    (net (code "103") (name "unconnected-(X1-{slash}CLK-PadA8)") (class "Default")
      (node (ref "X1") (pin "A8") (pinfunction "/CLK_A8") (pintype "bidirectional"))
    )
    (net (code "104") (name "unconnected-(X1-{slash}HALT-PadB15)") (class "Default")
      (node (ref "X1") (pin "B15") (pinfunction "/HALT_B15") (pintype "bidirectional"))
    )
    (net (code "105") (name "unconnected-(X1-{slash}INT-PadB13)") (class "Default")
      (node (ref "X1") (pin "B13") (pinfunction "/INT_B13") (pintype "bidirectional"))
    )
    (net (code "106") (name "unconnected-(X1-{slash}M1-PadB24)") (class "Default")
      (node (ref "X1") (pin "B24") (pinfunction "/M1_B24") (pintype "bidirectional"))
    )
    (net (code "107") (name "unconnected-(X1-{slash}MREQ-PadB16)") (class "Default")
      (node (ref "X1") (pin "B16") (pinfunction "/MREQ_B16") (pintype "bidirectional"))
    )
    (net (code "108") (name "unconnected-(X1-{slash}NMI-PadB14)") (class "Default")
      (node (ref "X1") (pin "B14") (pinfunction "/NMI_B14") (pintype "bidirectional"))
    )
    (net (code "109") (name "unconnected-(X1-{slash}RESET-PadA20)") (class "Default")
      (node (ref "X1") (pin "A20") (pinfunction "/RESET_A20") (pintype "bidirectional"))
    )
    (net (code "110") (name "unconnected-(X1-{slash}RFSH-PadB25)") (class "Default")
      (node (ref "X1") (pin "B25") (pinfunction "/RFSH_B25") (pintype "bidirectional"))
    )
    (net (code "111") (name "unconnected-(X1-{slash}ROMCS-PadA25)") (class "Default")
      (node (ref "X1") (pin "A25") (pinfunction "/ROMCS_A25") (pintype "bidirectional"))
    )
    (net (code "112") (name "unconnected-(X1-{slash}WAIT-PadB21)") (class "Default")
      (node (ref "X1") (pin "B21") (pinfunction "/WAIT_B21") (pintype "bidirectional"))
    )
  )
)
